# iface_schematic.net
KiCad netlist of a schematic drawn in EAGLE
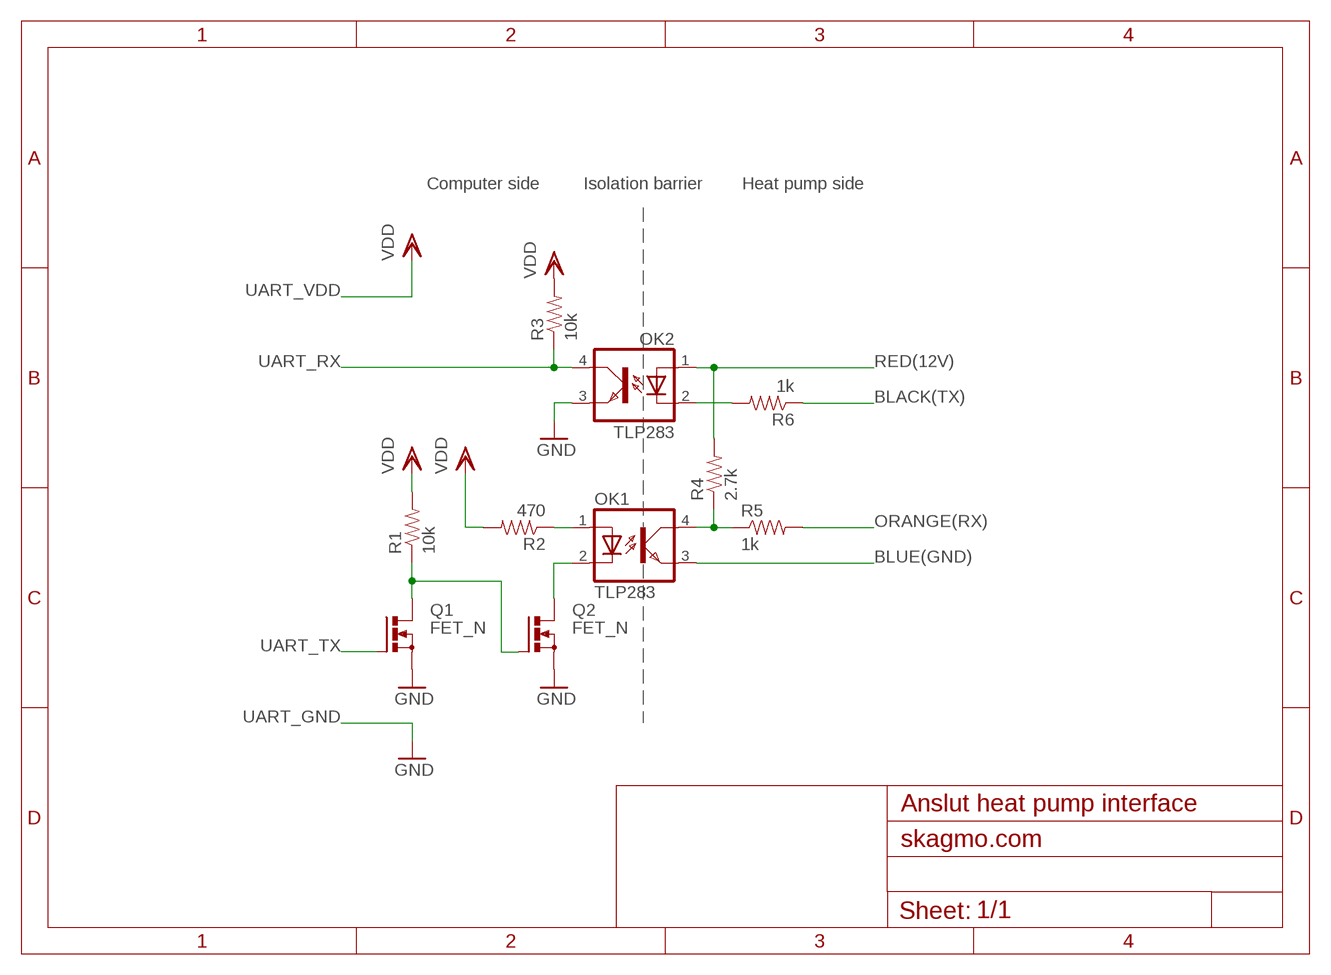
[diagram p0: schematic, sheet 1]

(export (version "E")
  (design (tool "Eeschema 10.0.6"))
  (components
    (comp (ref "OK1")
      (value "TLP283")
      (footprint "eagle-import:MINI-FLAT-4")
      (libsource (lib "eagle-import") (part "TLP283"))
    )
    (comp (ref "OK2")
      (value "TLP283")
      (footprint "eagle-import:MINI-FLAT-4")
      (libsource (lib "eagle-import") (part "TLP283"))
    )
    (comp (ref "Q1")
      (value "FET_N")
      (footprint "eagle-import:SOT23-3")
      (libsource (lib "eagle-import") (part "MOSFET_N_SOT23-3"))
    )
    (comp (ref "Q2")
      (value "FET_N")
      (footprint "eagle-import:SOT23-3")
      (libsource (lib "eagle-import") (part "MOSFET_N_SOT23-3"))
    )
    (comp (ref "R1")
      (value "10k")
      (footprint "eagle-import:0603")
      (libsource (lib "eagle-import") (part "RESISTOR0603"))
    )
    (comp (ref "R2")
      (value "470")
      (footprint "eagle-import:0603")
      (libsource (lib "eagle-import") (part "RESISTOR0603"))
    )
    (comp (ref "R3")
      (value "10k")
      (footprint "eagle-import:0603")
      (libsource (lib "eagle-import") (part "RESISTOR0603"))
    )
    (comp (ref "R4")
      (value "2.7k")
      (footprint "eagle-import:0603")
      (libsource (lib "eagle-import") (part "RESISTOR0603"))
    )
    (comp (ref "R5")
      (value "1k")
      (footprint "eagle-import:0603")
      (libsource (lib "eagle-import") (part "RESISTOR0603"))
    )
    (comp (ref "R6")
      (value "1k")
      (footprint "eagle-import:0603")
      (libsource (lib "eagle-import") (part "RESISTOR0603"))
    )
  )
  (nets
    (net (code "1") (name "/BLACK(TX)") (class "Default")
      (node (ref "R6") (pin "1") (pinfunction "1_1") (pintype "passive"))
    )
    (net (code "2") (name "/BLUE(GND)") (class "Default")
      (node (ref "OK1") (pin "3") (pinfunction "EMIT_3") (pintype "passive"))
    )
    (net (code "3") (name "/ORANGE(RX)") (class "Default")
      (node (ref "R5") (pin "2") (pinfunction "2_2") (pintype "passive"))
    )
    (net (code "4") (name "/RED(12V)") (class "Default")
      (node (ref "OK2") (pin "1") (pinfunction "A_1") (pintype "passive"))
      (node (ref "R4") (pin "2") (pinfunction "2_2") (pintype "passive"))
    )
    (net (code "5") (name "/UART_RX") (class "Default")
      (node (ref "OK2") (pin "4") (pinfunction "COL_4") (pintype "passive"))
      (node (ref "R3") (pin "1") (pinfunction "1_1") (pintype "passive"))
    )
    (net (code "6") (name "/UART_TX") (class "Default")
      (node (ref "Q1") (pin "1") (pinfunction "G_1") (pintype "passive"))
    )
    (net (code "7") (name "GND") (class "Default")
      (node (ref "OK2") (pin "3") (pinfunction "EMIT_3") (pintype "passive"))
      (node (ref "Q1") (pin "2") (pinfunction "S_2") (pintype "passive"))
      (node (ref "Q2") (pin "2") (pinfunction "S_2") (pintype "passive"))
    )
    (net (code "8") (name "Net-(OK1-A)") (class "Default")
      (node (ref "OK1") (pin "1") (pinfunction "A_1") (pintype "passive"))
      (node (ref "R2") (pin "1") (pinfunction "1_1") (pintype "passive"))
    )
    (net (code "9") (name "Net-(OK1-C)") (class "Default")
      (node (ref "OK1") (pin "2") (pinfunction "C_2") (pintype "passive"))
      (node (ref "Q2") (pin "3") (pinfunction "D_3") (pintype "passive"))
    )
    (net (code "10") (name "Net-(OK1-COL)") (class "Default")
      (node (ref "OK1") (pin "4") (pinfunction "COL_4") (pintype "passive"))
      (node (ref "R4") (pin "1") (pinfunction "1_1") (pintype "passive"))
      (node (ref "R5") (pin "1") (pinfunction "1_1") (pintype "passive"))
    )
    (net (code "11") (name "Net-(OK2-C)") (class "Default")
      (node (ref "OK2") (pin "2") (pinfunction "C_2") (pintype "passive"))
      (node (ref "R6") (pin "2") (pinfunction "2_2") (pintype "passive"))
    )
    (net (code "12") (name "Net-(Q1-D)") (class "Default")
      (node (ref "Q1") (pin "3") (pinfunction "D_3") (pintype "passive"))
      (node (ref "Q2") (pin "1") (pinfunction "G_1") (pintype "passive"))
      (node (ref "R1") (pin "1") (pinfunction "1_1") (pintype "passive"))
    )
    (net (code "13") (name "VDD") (class "Default")
      (node (ref "R1") (pin "2") (pinfunction "2_2") (pintype "passive"))
      (node (ref "R2") (pin "2") (pinfunction "2_2") (pintype "passive"))
      (node (ref "R3") (pin "2") (pinfunction "2_2") (pintype "passive"))
    )
  )
)
